# mftPlanetarium2-selfassemble.net
KiCad netlist of a schematic drawn in EAGLE
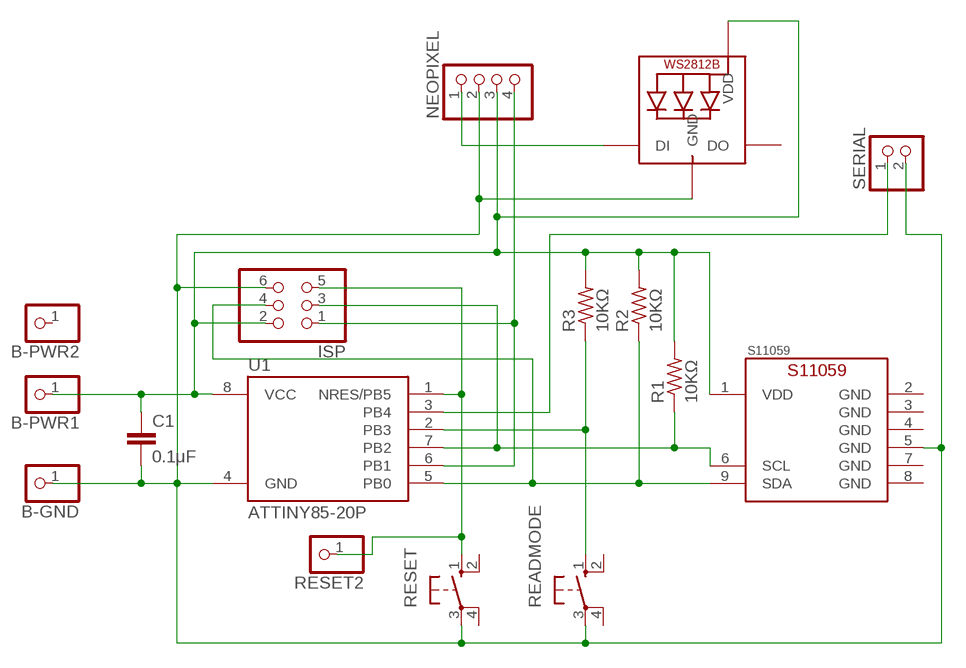
[diagram p0: schematic, sheet 1]

(export (version "E")
  (design (tool "Eeschema 10.0.6"))
  (components
    (comp (ref "B-GND")
      (value "PINHD-1X1")
      (footprint "eagle-import:1X01")
      (libsource (lib "eagle-import") (part "PINHD-1X1"))
    )
    (comp (ref "B-PWR1")
      (value "PINHD-1X1")
      (footprint "eagle-import:1X01")
      (libsource (lib "eagle-import") (part "PINHD-1X1"))
    )
    (comp (ref "B-PWR2")
      (value "PINHD-1X1")
      (footprint "eagle-import:1X01")
      (libsource (lib "eagle-import") (part "PINHD-1X1"))
    )
    (comp (ref "C1")
      (value "0.1μF")
      (footprint "eagle-import:C025-025X050")
      (libsource (lib "eagle-import") (part "C-EU025-025X050"))
    )
    (comp (ref "ISP")
      (value "PINHD-2X3")
      (footprint "eagle-import:2X03")
      (libsource (lib "eagle-import") (part "PINHD-2X3"))
    )
    (comp (ref "LED1")
      (value "WS2812B5050")
      (footprint "eagle-import:WS2812B")
      (libsource (lib "eagle-import") (part "WS2812B5050"))
    )
    (comp (ref "NEOPIXEL")
      (value "PINHD-1X4")
      (footprint "eagle-import:1X04")
      (libsource (lib "eagle-import") (part "PINHD-1X4"))
    )
    (comp (ref "R1")
      (value "10KΩ")
      (footprint "eagle-import:0204_7")
      (libsource (lib "eagle-import") (part "R-US_0204/7"))
    )
    (comp (ref "R2")
      (value "10KΩ")
      (footprint "eagle-import:0204_7")
      (libsource (lib "eagle-import") (part "R-US_0204/7"))
    )
    (comp (ref "R3")
      (value "10KΩ")
      (footprint "eagle-import:0204_7")
      (libsource (lib "eagle-import") (part "R-US_0204/7"))
    )
    (comp (ref "READMODE")
      (value "10-XX")
      (footprint "eagle-import:B3F-10XX")
      (fields (field (name "MPN") "B3F-1000"))
      (libsource (lib "eagle-import") (part "10-XX"))
    )
    (comp (ref "RESET")
      (value "10-XX")
      (footprint "eagle-import:B3F-10XX")
      (fields (field (name "MPN") "B3F-1000"))
      (libsource (lib "eagle-import") (part "10-XX"))
    )
    (comp (ref "RESET2")
      (value "PINHD-1X1")
      (footprint "eagle-import:1X01")
      (libsource (lib "eagle-import") (part "PINHD-1X1"))
    )
    (comp (ref "S11059")
      (value "S11059")
      (footprint "eagle-import:HAMAMATSU-S11059")
      (libsource (lib "eagle-import") (part "HAMAMATSU-S11059"))
    )
    (comp (ref "SERIAL")
      (value "PINHD-1X2")
      (footprint "eagle-import:1X02")
      (libsource (lib "eagle-import") (part "PINHD-1X2"))
    )
    (comp (ref "U1")
      (value "ATTINY85-20P")
      (footprint "eagle-import:PDIP08_300MIL")
      (libsource (lib "eagle-import") (part "ATTINY85P-20"))
    )
  )
  (nets
    (net (code "1") (name "Net-(LED1-DI)") (class "Default")
      (node (ref "LED1") (pin "4-DIN") (pinfunction "DI_4-DIN") (pintype "input"))
      (node (ref "NEOPIXEL") (pin "1") (pinfunction "1_1") (pintype "passive"))
    )
    (net (code "2") (name "Net-(LED1-GND)") (class "Default")
      (node (ref "B-GND") (pin "1") (pinfunction "1_1") (pintype "passive"))
      (node (ref "C1") (pin "2") (pinfunction "2_2") (pintype "passive"))
      (node (ref "ISP") (pin "6") (pinfunction "6_6") (pintype "passive"))
      (node (ref "LED1") (pin "3-GND") (pinfunction "GND_3-GND") (pintype "power_in"))
      (node (ref "NEOPIXEL") (pin "2") (pinfunction "2_2") (pintype "passive"))
      (node (ref "READMODE") (pin "3") (pinfunction "P_3") (pintype "passive"))
      (node (ref "RESET") (pin "3") (pinfunction "P_3") (pintype "passive"))
      (node (ref "S11059") (pin "5") (pinfunction "GND_5") (pintype "bidirectional"))
      (node (ref "SERIAL") (pin "2") (pinfunction "2_2") (pintype "passive"))
      (node (ref "U1") (pin "4") (pinfunction "GND_4") (pintype "power_in"))
    )
    (net (code "3") (name "Net-(LED1-VDD)") (class "Default")
      (node (ref "B-PWR1") (pin "1") (pinfunction "1_1") (pintype "passive"))
      (node (ref "C1") (pin "1") (pinfunction "1_1") (pintype "passive"))
      (node (ref "ISP") (pin "2") (pinfunction "2_2") (pintype "passive"))
      (node (ref "LED1") (pin "1-VDD") (pinfunction "VDD_1-VDD") (pintype "power_in"))
      (node (ref "NEOPIXEL") (pin "3") (pinfunction "3_3") (pintype "passive"))
      (node (ref "R1") (pin "2") (pinfunction "2_2") (pintype "passive"))
      (node (ref "R2") (pin "2") (pinfunction "2_2") (pintype "passive"))
      (node (ref "R3") (pin "2") (pinfunction "2_2") (pintype "passive"))
      (node (ref "S11059") (pin "1") (pinfunction "VDD_1") (pintype "bidirectional"))
      (node (ref "U1") (pin "8") (pinfunction "VCC_8") (pintype "power_in"))
    )
    (net (code "4") (name "Net-(READMODE-S)") (class "Default")
      (node (ref "R3") (pin "1") (pinfunction "1_1") (pintype "passive"))
      (node (ref "READMODE") (pin "1") (pinfunction "S_1") (pintype "passive"))
      (node (ref "U1") (pin "2") (pinfunction "PB3_2") (pintype "bidirectional"))
    )
    (net (code "5") (name "Net-(RESET-S)") (class "Default")
      (node (ref "ISP") (pin "5") (pinfunction "5_5") (pintype "passive"))
      (node (ref "RESET") (pin "1") (pinfunction "S_1") (pintype "passive"))
      (node (ref "RESET2") (pin "1") (pinfunction "1_1") (pintype "passive"))
      (node (ref "U1") (pin "1") (pinfunction "NRES/PB5_1") (pintype "bidirectional"))
    )
    (net (code "6") (name "Net-(S11059-SCL)") (class "Default")
      (node (ref "ISP") (pin "3") (pinfunction "3_3") (pintype "passive"))
      (node (ref "R1") (pin "1") (pinfunction "1_1") (pintype "passive"))
      (node (ref "S11059") (pin "6") (pinfunction "SCL_6") (pintype "bidirectional"))
      (node (ref "U1") (pin "7") (pinfunction "PB2_7") (pintype "bidirectional"))
    )
    (net (code "7") (name "Net-(S11059-SDA)") (class "Default")
      (node (ref "ISP") (pin "4") (pinfunction "4_4") (pintype "passive"))
      (node (ref "R2") (pin "1") (pinfunction "1_1") (pintype "passive"))
      (node (ref "S11059") (pin "9") (pinfunction "SDA_9") (pintype "bidirectional"))
      (node (ref "U1") (pin "5") (pinfunction "PB0_5") (pintype "bidirectional"))
    )
    (net (code "8") (name "Net-(U1-PB1)") (class "Default")
      (node (ref "ISP") (pin "1") (pinfunction "1_1") (pintype "passive"))
      (node (ref "NEOPIXEL") (pin "4") (pinfunction "4_4") (pintype "passive"))
      (node (ref "U1") (pin "6") (pinfunction "PB1_6") (pintype "bidirectional"))
    )
    (net (code "9") (name "Net-(U1-PB4)") (class "Default")
      (node (ref "SERIAL") (pin "1") (pinfunction "1_1") (pintype "passive"))
      (node (ref "U1") (pin "3") (pinfunction "PB4_3") (pintype "bidirectional"))
    )
    (net (code "10") (name "unconnected-(B-PWR2-Pad1)") (class "Default")
      (node (ref "B-PWR2") (pin "1") (pinfunction "1_1") (pintype "passive"))
    )
    (net (code "11") (name "unconnected-(LED1-DO-Pad2-DOUT)") (class "Default")
      (node (ref "LED1") (pin "2-DOUT") (pinfunction "DO_2-DOUT") (pintype "output"))
    )
    (net (code "12") (name "unconnected-(READMODE-P1-Pad4)") (class "Default")
      (node (ref "READMODE") (pin "4") (pinfunction "P1_4") (pintype "passive"))
    )
    (net (code "13") (name "unconnected-(READMODE-S1-Pad2)") (class "Default")
      (node (ref "READMODE") (pin "2") (pinfunction "S1_2") (pintype "passive"))
    )
    (net (code "14") (name "unconnected-(RESET-P1-Pad4)") (class "Default")
      (node (ref "RESET") (pin "4") (pinfunction "P1_4") (pintype "passive"))
    )
    (net (code "15") (name "unconnected-(RESET-S1-Pad2)") (class "Default")
      (node (ref "RESET") (pin "2") (pinfunction "S1_2") (pintype "passive"))
    )
    (net (code "16") (name "unconnected-(S11059-GND-Pad2)") (class "Default")
      (node (ref "S11059") (pin "2") (pinfunction "GND_2") (pintype "bidirectional"))
    )
    (net (code "17") (name "unconnected-(S11059-GND-Pad3)") (class "Default")
      (node (ref "S11059") (pin "3") (pinfunction "GND_3") (pintype "bidirectional"))
    )
    (net (code "18") (name "unconnected-(S11059-GND-Pad4)") (class "Default")
      (node (ref "S11059") (pin "4") (pinfunction "GND_4") (pintype "bidirectional"))
    )
    (net (code "19") (name "unconnected-(S11059-GND-Pad7)") (class "Default")
      (node (ref "S11059") (pin "7") (pinfunction "GND_7") (pintype "bidirectional"))
    )
    (net (code "20") (name "unconnected-(S11059-GND-Pad8)") (class "Default")
      (node (ref "S11059") (pin "8") (pinfunction "GND_8") (pintype "bidirectional"))
    )
  )
)
